# passeBas.net
KiCad netlist of a schematic drawn in Altium Designer
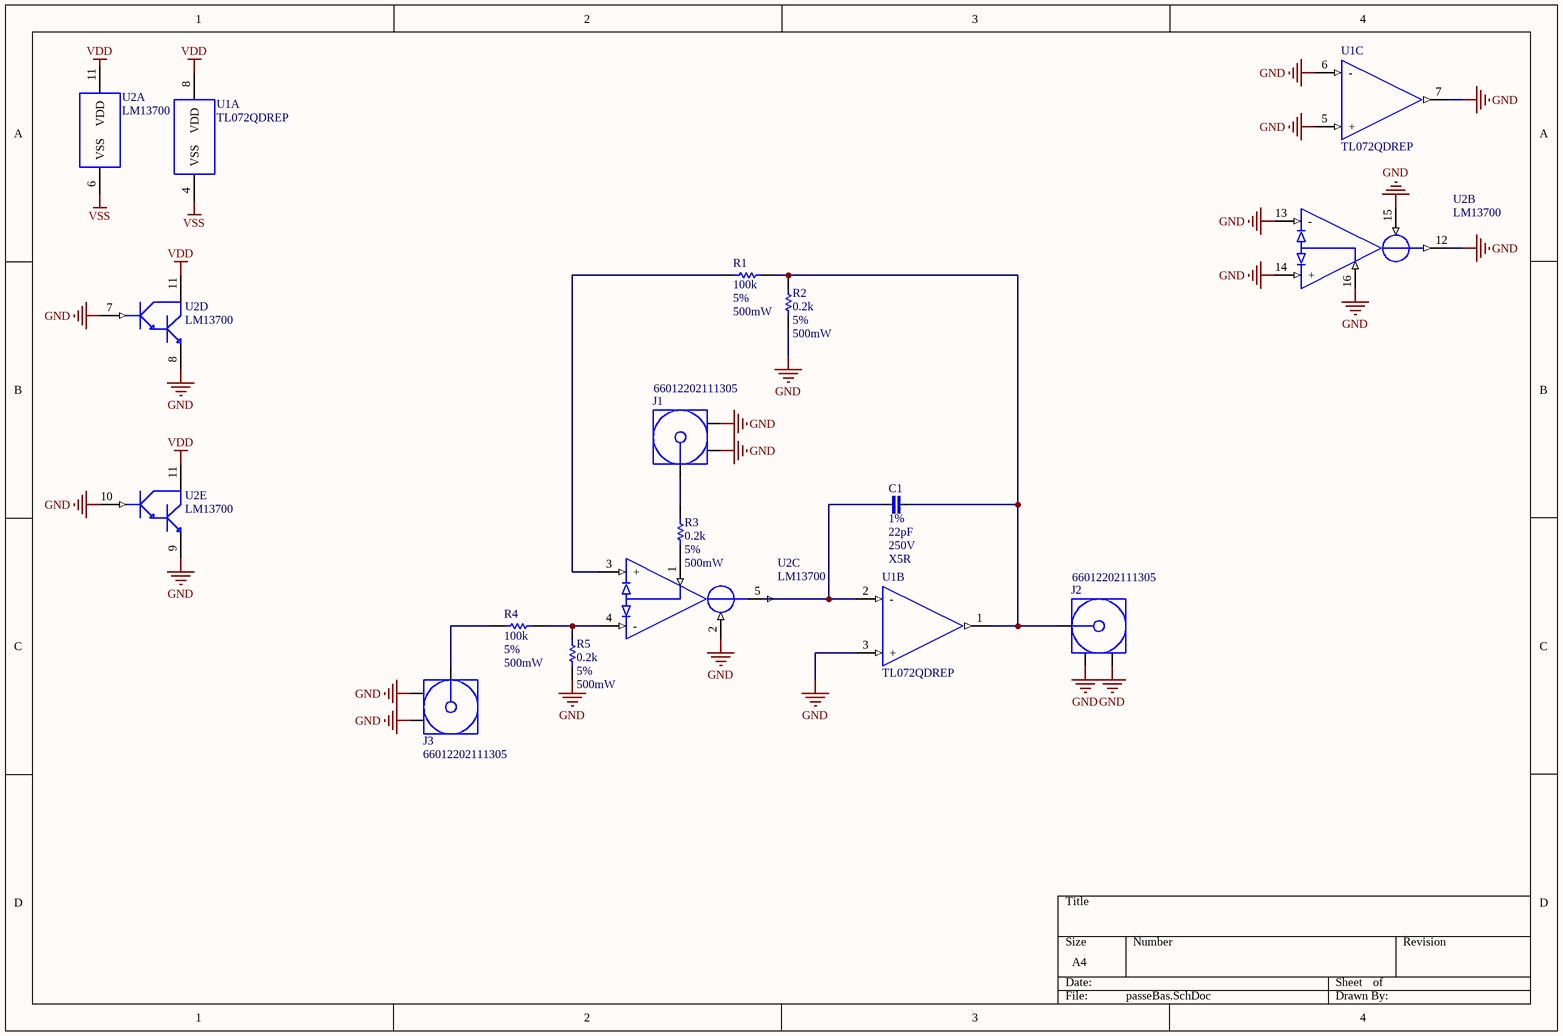
[diagram p0: passeBas.SchDoc]

(export (version "E")
  (design (tool "Eeschema 10.0.6"))
  (components
    (comp (ref "C1")
      (value "22pF")
      (footprint "0805")
      (description "Capacitor 22pF 250V 10% X5R 0805")
      (fields
        (field (name "TOL") "1%")
        (field (name "TENSION") "250V")
        (field (name "TECH") "X5R")
        (field (name "Comment") "Capacitor_22pF_250V_1%_X5R_0805")
      )
      (libsource (lib "4AE_LM_update") (part "Capacitor_22pF_250V_1%_X5R_0805"))
    )
    (comp (ref "J1")
      (value "MMCX_66012202111305")
      (footprint "MMCX_66012202111305")
      (description "Connecteur MMCX  horizontal SMD")
      (fields (field (name "REF") "66012202111305"))
      (libsource (lib "4AE_LM_update") (part "MMCX_66012202111305"))
    )
    (comp (ref "J2")
      (value "MMCX_66012202111305")
      (footprint "MMCX_66012202111305")
      (description "Connecteur MMCX  horizontal SMD")
      (fields (field (name "REF") "66012202111305"))
      (libsource (lib "4AE_LM_update") (part "MMCX_66012202111305"))
    )
    (comp (ref "J3")
      (value "MMCX_66012202111305")
      (footprint "MMCX_66012202111305")
      (description "Connecteur MMCX  horizontal SMD")
      (fields (field (name "REF") "66012202111305"))
      (libsource (lib "4AE_LM_update") (part "MMCX_66012202111305"))
    )
    (comp (ref "R1")
      (value "100k")
      (footprint "0805_RES")
      (description "Resistor  100k 5% 500mW 0805")
      (fields
        (field (name "VOLTAGE") "150V")
        (field (name "TOL") "5%")
        (field (name "POWER") "500mW")
        (field (name "Comment") "Resistor_100k_5%_500mW_0805")
      )
      (libsource (lib "4AE_LM_update") (part "Resistor_100k_5%_500mW_0805"))
    )
    (comp (ref "R2")
      (value "0.2k")
      (footprint "0805_RES")
      (description "Resistor  0.2k 5% 500mW 0805")
      (fields
        (field (name "VOLTAGE") "150V")
        (field (name "TOL") "5%")
        (field (name "POWER") "500mW")
        (field (name "Comment") "Resistor_0.2k_5%_500mW_0805")
      )
      (libsource (lib "4AE_LM_update") (part "Resistor_0.2k_5%_500mW_0805"))
    )
    (comp (ref "R3")
      (value "0.2k")
      (footprint "0805_RES")
      (description "Resistor  56k 5% 500mW 0805")
      (fields
        (field (name "VOLTAGE") "150V")
        (field (name "TOL") "5%")
        (field (name "POWER") "500mW")
        (field (name "Comment") "Resistor_56k_5%_500mW_0805")
      )
      (libsource (lib "4AE_LM_update") (part "Resistor_56k_5%_500mW_0805"))
    )
    (comp (ref "R4")
      (value "100k")
      (footprint "0805_RES")
      (description "Resistor  100k 5% 500mW 0805")
      (fields
        (field (name "VOLTAGE") "150V")
        (field (name "TOL") "5%")
        (field (name "POWER") "500mW")
        (field (name "Comment") "Resistor_100k_5%_500mW_0805")
      )
      (libsource (lib "4AE_LM_update") (part "Resistor_100k_5%_500mW_0805"))
    )
    (comp (ref "R5")
      (value "0.2k")
      (footprint "0805_RES")
      (description "Resistor  0.2k 5% 500mW 0805")
      (fields
        (field (name "VOLTAGE") "150V")
        (field (name "TOL") "5%")
        (field (name "POWER") "500mW")
        (field (name "Comment") "Resistor_0.2k_5%_500mW_0805")
      )
      (libsource (lib "4AE_LM_update") (part "Resistor_0.2k_5%_500mW_0805"))
    )
    (comp (ref "U1")
      (value "AOP_TL072QDREP")
      (footprint "SOIC8")
      (description "low noise Jfet input amplifier")
      (fields (field (name "REF") "TL072QDREP"))
      (libsource (lib "4AE_LM_update") (part "AOP_TL072QDREP"))
    )
    (comp (ref "U2")
      (value "LM13700")
      (footprint "SOIC16L")
      (description "OTA")
      (fields (field (name "REF") "LM13700"))
      (libsource (lib "4AE_LM_update") (part "OTA_LM13700"))
    )
  )
  (nets
    (net (code "1") (name "GND") (class "Default")
      (node (ref "J1") (pin "2") (pinfunction "GND_2") (pintype "power_in"))
      (node (ref "J1") (pin "3") (pinfunction "GND_3") (pintype "power_in"))
      (node (ref "J2") (pin "2") (pinfunction "GND_2") (pintype "power_in"))
      (node (ref "J2") (pin "3") (pinfunction "GND_3") (pintype "power_in"))
      (node (ref "J3") (pin "2") (pinfunction "GND_2") (pintype "power_in"))
      (node (ref "J3") (pin "3") (pinfunction "GND_3") (pintype "power_in"))
      (node (ref "R2") (pin "1") (pinfunction "1_1") (pintype "passive"))
      (node (ref "R5") (pin "1") (pinfunction "1_1") (pintype "passive"))
      (node (ref "U1") (pin "3") (pinfunction "+_3") (pintype "input"))
      (node (ref "U1") (pin "5") (pinfunction "+_5") (pintype "input"))
      (node (ref "U1") (pin "6") (pinfunction "-_6") (pintype "input"))
      (node (ref "U1") (pin "7") (pinfunction "outB_7") (pintype "output"))
      (node (ref "U2") (pin "10") (pintype "input"))
      (node (ref "U2") (pin "12") (pinfunction "outA_12") (pintype "output"))
      (node (ref "U2") (pin "13") (pinfunction "-_13") (pintype "input"))
      (node (ref "U2") (pin "14") (pinfunction "+_14") (pintype "input"))
      (node (ref "U2") (pin "15") (pintype "input"))
      (node (ref "U2") (pin "16") (pintype "input"))
      (node (ref "U2") (pin "2") (pintype "input"))
      (node (ref "U2") (pin "7") (pintype "input"))
      (node (ref "U2") (pin "8") (pintype "power_in"))
      (node (ref "U2") (pin "9") (pintype "power_in"))
    )
    (net (code "2") (name "Net-(J1-Signal)") (class "Default")
      (node (ref "J1") (pin "1") (pinfunction "Signal_1") (pintype "passive"))
      (node (ref "R3") (pin "2") (pinfunction "2_2") (pintype "passive"))
    )
    (net (code "3") (name "Net-(J2-Signal)") (class "Default")
      (node (ref "C1") (pin "2") (pinfunction "2_2") (pintype "passive"))
      (node (ref "J2") (pin "1") (pinfunction "Signal_1") (pintype "passive"))
      (node (ref "R1") (pin "2") (pinfunction "2_2") (pintype "passive"))
      (node (ref "R2") (pin "2") (pinfunction "2_2") (pintype "passive"))
      (node (ref "U1") (pin "1") (pinfunction "outA_1") (pintype "output"))
    )
    (net (code "4") (name "Net-(J3-Signal)") (class "Default")
      (node (ref "J3") (pin "1") (pinfunction "Signal_1") (pintype "passive"))
      (node (ref "R4") (pin "2") (pinfunction "2_2") (pintype "passive"))
    )
    (net (code "5") (name "Net-(R3-Pad1)") (class "Default")
      (node (ref "R3") (pin "1") (pinfunction "1_1") (pintype "passive"))
      (node (ref "U2") (pin "1") (pintype "input"))
    )
    (net (code "6") (name "Net-(U1B--)") (class "Default")
      (node (ref "C1") (pin "1") (pinfunction "1_1") (pintype "passive"))
      (node (ref "U1") (pin "2") (pinfunction "-_2") (pintype "input"))
    )
    (net (code "7") (name "Net-(U2C-+)") (class "Default")
      (node (ref "R1") (pin "1") (pinfunction "1_1") (pintype "passive"))
      (node (ref "U2") (pin "3") (pinfunction "+_3") (pintype "input"))
    )
    (net (code "8") (name "Net-(U2C--)") (class "Default")
      (node (ref "R4") (pin "1") (pinfunction "1_1") (pintype "passive"))
      (node (ref "R5") (pin "2") (pinfunction "2_2") (pintype "passive"))
      (node (ref "U2") (pin "4") (pinfunction "-_4") (pintype "input"))
    )
    (net (code "9") (name "VDD") (class "Default")
      (node (ref "U1") (pin "8") (pinfunction "VDD_8") (pintype "power_in"))
      (node (ref "U2") (pin "11") (pinfunction "VDD_11") (pintype "power_in"))
    )
    (net (code "10") (name "VSS") (class "Default")
      (node (ref "U1") (pin "4") (pinfunction "VSS_4") (pintype "power_in"))
      (node (ref "U2") (pin "6") (pinfunction "VSS_6") (pintype "power_in"))
    )
    (net (code "11") (name "unconnected-(U2-Pad5)") (class "Default")
      (node (ref "U2") (pin "5") (pintype "input"))
    )
    (net (code "12") (name "unconnected-(U2A-VDD-Pad11)") (class "Default")
      (node (ref "U2") (pin "11") (pinfunction "VDD_11") (pintype "power_in"))
    )
  )
)
